# Battery_Management.net
KiCad netlist of a schematic drawn in Altium Designer
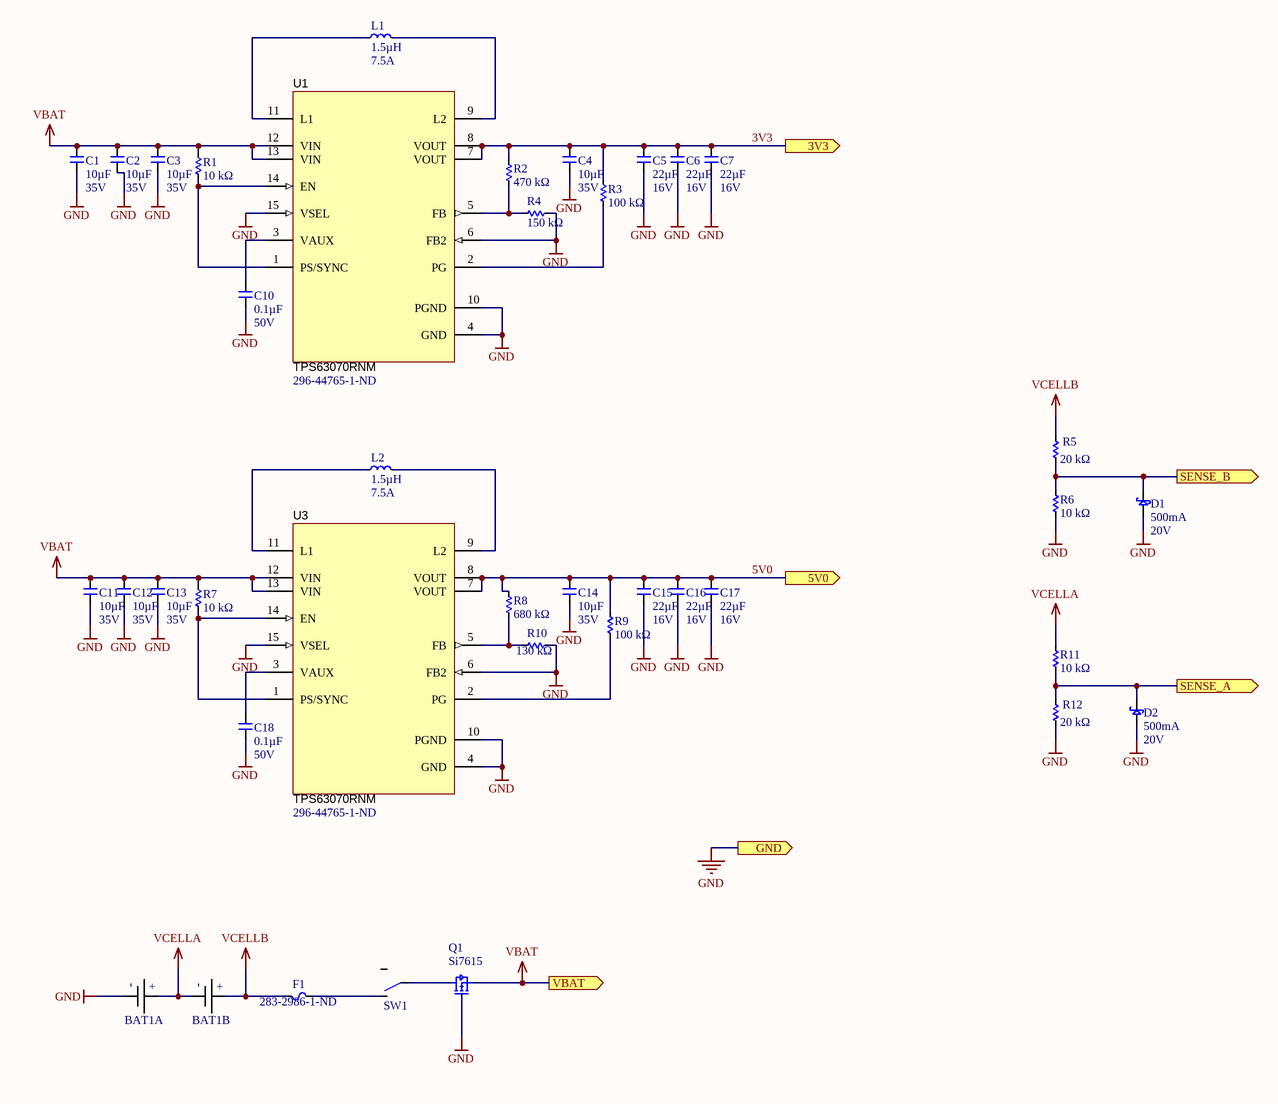
[diagram p0: Battery_Management.SchDoc]

(export (version "E")
  (design (tool "Eeschema 10.0.6"))
  (components
    (comp (ref "BAT1")
      (value "BATT_Clip_Li-Ion_2x")
      (footprint "BATT_18650_KEYSTONE_1048")
      (description "Dual Lithium Ion Cell Holder")
      (fields
        (field (name "MANUFACTURER") "Keystone Electronics")
        (field (name "MANUFACTURER PART NUMBER") "1048P")
      )
      (libsource (lib "connector") (part "BATT_Clip_Li-Ion_2x"))
    )
    (comp (ref "C1")
      (value "__template_cap")
      (footprint "C0603")
      (fields
        (field (name "CAPACITANCE (SHORTHAND)") "10µF")
        (field (name "RATED VOLTAGE") "35V")
        (field (name "MANUFACTURER") "Murata Electronics North America")
      )
      (libsource (lib "passives") (part "__template_cap"))
    )
    (comp (ref "C2")
      (value "__template_cap")
      (footprint "C0603")
      (fields
        (field (name "CAPACITANCE (SHORTHAND)") "10µF")
        (field (name "RATED VOLTAGE") "35V")
        (field (name "MANUFACTURER") "Murata Electronics North America")
      )
      (libsource (lib "passives") (part "__template_cap"))
    )
    (comp (ref "C3")
      (value "__template_cap")
      (footprint "C0603")
      (fields
        (field (name "CAPACITANCE (SHORTHAND)") "10µF")
        (field (name "RATED VOLTAGE") "35V")
        (field (name "MANUFACTURER") "Murata Electronics North America")
      )
      (libsource (lib "passives") (part "__template_cap"))
    )
    (comp (ref "C4")
      (value "__template_cap")
      (footprint "C0603")
      (fields
        (field (name "CAPACITANCE (SHORTHAND)") "10µF")
        (field (name "RATED VOLTAGE") "35V")
        (field (name "MANUFACTURER") "Murata Electronics North America")
      )
      (libsource (lib "passives") (part "__template_cap"))
    )
    (comp (ref "C5")
      (value "__template_cap")
      (footprint "C0603")
      (fields
        (field (name "CAPACITANCE (SHORTHAND)") "22µF")
        (field (name "RATED VOLTAGE") "16V")
        (field (name "MANUFACTURER") "Samsung Electro-Mechanics")
      )
      (libsource (lib "passives") (part "__template_cap"))
    )
    (comp (ref "C6")
      (value "__template_cap")
      (footprint "C0603")
      (fields
        (field (name "CAPACITANCE (SHORTHAND)") "22µF")
        (field (name "RATED VOLTAGE") "16V")
        (field (name "MANUFACTURER") "Samsung Electro-Mechanics")
      )
      (libsource (lib "passives") (part "__template_cap"))
    )
    (comp (ref "C7")
      (value "__template_cap")
      (footprint "C0603")
      (fields
        (field (name "CAPACITANCE (SHORTHAND)") "22µF")
        (field (name "RATED VOLTAGE") "16V")
        (field (name "MANUFACTURER") "Samsung Electro-Mechanics")
      )
      (libsource (lib "passives") (part "__template_cap"))
    )
    (comp (ref "C10")
      (value "__template_cap")
      (footprint "C0603")
      (fields
        (field (name "CAPACITANCE (SHORTHAND)") "0.1µF")
        (field (name "RATED VOLTAGE") "50V")
        (field (name "MANUFACTURER") "Murata Electronics North America")
      )
      (libsource (lib "passives") (part "__template_cap"))
    )
    (comp (ref "C11")
      (value "__template_cap")
      (footprint "C0603")
      (fields
        (field (name "CAPACITANCE (SHORTHAND)") "10µF")
        (field (name "RATED VOLTAGE") "35V")
        (field (name "MANUFACTURER") "Murata Electronics North America")
      )
      (libsource (lib "passives") (part "__template_cap"))
    )
    (comp (ref "C12")
      (value "__template_cap")
      (footprint "C0603")
      (fields
        (field (name "CAPACITANCE (SHORTHAND)") "10µF")
        (field (name "RATED VOLTAGE") "35V")
        (field (name "MANUFACTURER") "Murata Electronics North America")
      )
      (libsource (lib "passives") (part "__template_cap"))
    )
    (comp (ref "C13")
      (value "__template_cap")
      (footprint "C0603")
      (fields
        (field (name "CAPACITANCE (SHORTHAND)") "10µF")
        (field (name "RATED VOLTAGE") "35V")
        (field (name "MANUFACTURER") "Murata Electronics North America")
      )
      (libsource (lib "passives") (part "__template_cap"))
    )
    (comp (ref "C14")
      (value "__template_cap")
      (footprint "C0603")
      (fields
        (field (name "CAPACITANCE (SHORTHAND)") "10µF")
        (field (name "RATED VOLTAGE") "35V")
        (field (name "MANUFACTURER") "Murata Electronics North America")
      )
      (libsource (lib "passives") (part "__template_cap"))
    )
    (comp (ref "C15")
      (value "__template_cap")
      (footprint "C0603")
      (fields
        (field (name "CAPACITANCE (SHORTHAND)") "22µF")
        (field (name "RATED VOLTAGE") "16V")
        (field (name "MANUFACTURER") "Samsung Electro-Mechanics")
      )
      (libsource (lib "passives") (part "__template_cap"))
    )
    (comp (ref "C16")
      (value "__template_cap")
      (footprint "C0603")
      (fields
        (field (name "CAPACITANCE (SHORTHAND)") "22µF")
        (field (name "RATED VOLTAGE") "16V")
        (field (name "MANUFACTURER") "Samsung Electro-Mechanics")
      )
      (libsource (lib "passives") (part "__template_cap"))
    )
    (comp (ref "C17")
      (value "__template_cap")
      (footprint "C0603")
      (fields
        (field (name "CAPACITANCE (SHORTHAND)") "22µF")
        (field (name "RATED VOLTAGE") "16V")
        (field (name "MANUFACTURER") "Samsung Electro-Mechanics")
      )
      (libsource (lib "passives") (part "__template_cap"))
    )
    (comp (ref "C18")
      (value "__template_cap")
      (footprint "C0603")
      (fields
        (field (name "CAPACITANCE (SHORTHAND)") "0.1µF")
        (field (name "RATED VOLTAGE") "50V")
        (field (name "MANUFACTURER") "Murata Electronics North America")
      )
      (libsource (lib "passives") (part "__template_cap"))
    )
    (comp (ref "D1")
      (value "SCHOTTKY_MBR0520L")
      (footprint "SOD123")
      (description "DIODE SCHOTTKY 0.5A 20V SOD-123")
      (fields
        (field (name "MANUFACTURER") "Fairchild Semiconductor")
        (field (name "MANUFACTURER PART NUMBER") "MBR0520L")
        (field (name "CURRENT - AVERAGE RECTIFIED (IO)") "500mA")
        (field (name "VOLTAGE - DC REVERSE (VR) (MAX)") "20V")
      )
      (libsource (lib "SSI") (part "SCHOTTKY_MBR0520L"))
    )
    (comp (ref "D2")
      (value "SCHOTTKY_MBR0520L")
      (footprint "SOD123")
      (description "DIODE SCHOTTKY 0.5A 20V SOD-123")
      (fields
        (field (name "MANUFACTURER") "Fairchild Semiconductor")
        (field (name "MANUFACTURER PART NUMBER") "MBR0520L")
        (field (name "CURRENT - AVERAGE RECTIFIED (IO)") "500mA")
        (field (name "VOLTAGE - DC REVERSE (VR) (MAX)") "20V")
      )
      (libsource (lib "SSI") (part "SCHOTTKY_MBR0520L"))
    )
    (comp (ref "F1")
      (value "__template_fuse")
      (footprint "R1206")
      (fields
        (field (name "SUPPLIER PART NUMBER 1") "283-2986-1-ND")
        (field (name "MANUFACTURER") "Eaton")
        (field (name "MANUFACTURER PART NUMBER") "CC12H5A-TR")
      )
      (libsource (lib "SSI") (part "__template_fuse"))
    )
    (comp (ref "L1")
      (value "IND_IHLP2020CZER1R5M11")
      (footprint "SMD5230")
      (description "INDUCTOR POWER 1.5UH 7.5A SMD")
      (fields
        (field (name "MANUFACTURER") "Vishay Dale")
        (field (name "MANUFACTURER PART NUMBER") "IHLP2020CZER1R5M11")
        (field (name "INDUCTANCE") "1.5µH")
        (field (name "CURRENT RATING") "7.5A")
      )
      (libsource (lib "SSI") (part "IND_IHLP2020CZER1R5M11"))
    )
    (comp (ref "L2")
      (value "IND_IHLP2020CZER1R5M11")
      (footprint "SMD5230")
      (description "INDUCTOR POWER 1.5UH 7.5A SMD")
      (fields
        (field (name "MANUFACTURER") "Vishay Dale")
        (field (name "MANUFACTURER PART NUMBER") "IHLP2020CZER1R5M11")
        (field (name "INDUCTANCE") "1.5µH")
        (field (name "CURRENT RATING") "7.5A")
      )
      (libsource (lib "SSI") (part "IND_IHLP2020CZER1R5M11"))
    )
    (comp (ref "Q1")
      (value "Si7615")
      (footprint "POWERPAK_1212-8_SINGLE")
      (description "MOSFET P-CH 20V 35A PPK")
      (fields
        (field (name "MANUFACTURER") "Vishay Siliconix")
        (field (name "MANUFACTURER PART NUMBER") "SI7615ADN-T1-GE3")
      )
      (libsource (lib "SSI") (part "PFET_SI7615ADN-T1"))
    )
    (comp (ref "R1")
      (value "__template_resistor")
      (footprint "R0603")
      (fields
        (field (name "RESISTANCE") "10 kΩ")
        (field (name "MANUFACTURER PART NUMBER") "RC0603FR-0710KL")
        (field (name "MANUFACTURER") "Yageo")
        (field (name "TOLERANCE") "±1%")
      )
      (libsource (lib "passives") (part "__template_resistor"))
    )
    (comp (ref "R2")
      (value "RC0603FR-07470KL")
      (footprint "R0603")
      (fields
        (field (name "MANUFACTURER") "Yageo")
        (field (name "TOLERANCE") "±1%")
        (field (name "RESISTANCE") "470 kΩ")
      )
      (libsource (lib "passives") (part "__template_resistor"))
    )
    (comp (ref "R3")
      (value "RC0603FR-07100KL")
      (footprint "R0603")
      (fields
        (field (name "MANUFACTURER") "Yageo")
        (field (name "TOLERANCE") "±1%")
        (field (name "RESISTANCE") "100 kΩ")
      )
      (libsource (lib "passives") (part "__template_resistor"))
    )
    (comp (ref "R4")
      (value "RC0603FR-07150KL")
      (footprint "R0603")
      (fields
        (field (name "MANUFACTURER") "Yageo")
        (field (name "TOLERANCE") "±1%")
        (field (name "RESISTANCE") "150 kΩ")
      )
      (libsource (lib "passives") (part "__template_resistor"))
    )
    (comp (ref "R5")
      (value "__template_resistor")
      (footprint "R0603")
      (fields
        (field (name "RESISTANCE") "20 kΩ")
        (field (name "MANUFACTURER PART NUMBER") "RC0603FR-0720KL")
        (field (name "MANUFACTURER") "Yageo")
        (field (name "TOLERANCE") "±1%")
      )
      (libsource (lib "passives") (part "__template_resistor"))
    )
    (comp (ref "R6")
      (value "__template_resistor")
      (footprint "R0603")
      (fields
        (field (name "RESISTANCE") "10 kΩ")
        (field (name "MANUFACTURER PART NUMBER") "RC0603FR-0710KL")
        (field (name "MANUFACTURER") "Yageo")
        (field (name "TOLERANCE") "±1%")
      )
      (libsource (lib "passives") (part "__template_resistor"))
    )
    (comp (ref "R7")
      (value "__template_resistor")
      (footprint "R0603")
      (fields
        (field (name "RESISTANCE") "10 kΩ")
        (field (name "MANUFACTURER PART NUMBER") "RC0603FR-0710KL")
        (field (name "MANUFACTURER") "Yageo")
        (field (name "TOLERANCE") "±1%")
      )
      (libsource (lib "passives") (part "__template_resistor"))
    )
    (comp (ref "R8")
      (value "RC0603FR-07680KL")
      (footprint "R0603")
      (fields
        (field (name "MANUFACTURER") "Yageo")
        (field (name "TOLERANCE") "±1%")
        (field (name "RESISTANCE") "680 kΩ")
      )
      (libsource (lib "passives") (part "__template_resistor"))
    )
    (comp (ref "R9")
      (value "RC0603FR-07100KL")
      (footprint "R0603")
      (fields
        (field (name "MANUFACTURER") "Yageo")
        (field (name "TOLERANCE") "±1%")
        (field (name "RESISTANCE") "100 kΩ")
      )
      (libsource (lib "passives") (part "__template_resistor"))
    )
    (comp (ref "R10")
      (value "RC0603FR-07130KL")
      (footprint "R0603")
      (fields
        (field (name "MANUFACTURER") "Yageo")
        (field (name "TOLERANCE") "±1%")
        (field (name "RESISTANCE") "130 kΩ")
      )
      (libsource (lib "passives") (part "__template_resistor"))
    )
    (comp (ref "R11")
      (value "__template_resistor")
      (footprint "R0603")
      (fields
        (field (name "RESISTANCE") "10 kΩ")
        (field (name "MANUFACTURER PART NUMBER") "RC0603FR-0710KL")
        (field (name "MANUFACTURER") "Yageo")
        (field (name "TOLERANCE") "±1%")
      )
      (libsource (lib "passives") (part "__template_resistor"))
    )
    (comp (ref "R12")
      (value "__template_resistor")
      (footprint "R0603")
      (fields
        (field (name "RESISTANCE") "20 kΩ")
        (field (name "MANUFACTURER PART NUMBER") "RC0603FR-0720KL")
        (field (name "MANUFACTURER") "Yageo")
        (field (name "TOLERANCE") "±1%")
      )
      (libsource (lib "passives") (part "__template_resistor"))
    )
    (comp (ref "SW1")
      (value "~")
      (footprint "SWITCH_500SSP1S1M6QEA")
      (description "SWITCH SLIDE SPDT R/A 5A")
      (fields
        (field (name "MANUFACTURER") "E-Switch")
        (field (name "MANUFACTURER PART NUMBER") "500SSP1S1M6QEA")
      )
      (libsource (lib "SSI") (part "SWITCH_500SSP1S1M6QEA"))
    )
    (comp (ref "U1")
      (value "TPS63070RNM")
      (footprint "TPS63070")
      (description "BUCKBOOST TPS63070RNM, RNM0015A")
      (fields
        (field (name "MANUFACTURER") "Texas Instruments")
        (field (name "SUPPLIER PART NUMBER 1") "296-44765-1-ND")
        (field (name "SYMBOLCREATOR") "Altium")
        (field (name "PUBLISHER") "Texas Instruments")
      )
      (libsource (lib "SSI") (part "TPS63070RNM"))
    )
    (comp (ref "U3")
      (value "TPS63070RNM")
      (footprint "TPS63070")
      (description "BUCKBOOST TPS63070RNM, RNM0015A")
      (fields
        (field (name "MANUFACTURER") "Texas Instruments")
        (field (name "SUPPLIER PART NUMBER 1") "296-44765-1-ND")
        (field (name "SYMBOLCREATOR") "Altium")
        (field (name "PUBLISHER") "Texas Instruments")
      )
      (libsource (lib "SSI") (part "TPS63070RNM"))
    )
  )
  (nets
    (net (code "1") (name "/3V3") (class "Default")
      (node (ref "C4") (pin "1") (pintype "passive"))
      (node (ref "C5") (pin "1") (pintype "passive"))
      (node (ref "C6") (pin "1") (pintype "passive"))
      (node (ref "C7") (pin "1") (pintype "passive"))
      (node (ref "R2") (pin "2") (pintype "passive"))
      (node (ref "R3") (pin "2") (pintype "passive"))
      (node (ref "U1") (pin "7") (pinfunction "VOUT_7") (pintype "power_in"))
      (node (ref "U1") (pin "8") (pinfunction "VOUT_8") (pintype "power_in"))
    )
    (net (code "2") (name "/5V0") (class "Default")
      (node (ref "C14") (pin "1") (pintype "passive"))
      (node (ref "C15") (pin "1") (pintype "passive"))
      (node (ref "C16") (pin "1") (pintype "passive"))
      (node (ref "C17") (pin "1") (pintype "passive"))
      (node (ref "R8") (pin "2") (pintype "passive"))
      (node (ref "R9") (pin "2") (pintype "passive"))
      (node (ref "U3") (pin "7") (pinfunction "VOUT_7") (pintype "power_in"))
      (node (ref "U3") (pin "8") (pinfunction "VOUT_8") (pintype "power_in"))
    )
    (net (code "3") (name "/SENSE_A") (class "Default")
      (node (ref "D2") (pin "2") (pintype "passive"))
      (node (ref "R11") (pin "1") (pintype "passive"))
      (node (ref "R12") (pin "2") (pintype "passive"))
    )
    (net (code "4") (name "/SENSE_B") (class "Default")
      (node (ref "D1") (pin "2") (pintype "passive"))
      (node (ref "R5") (pin "1") (pintype "passive"))
      (node (ref "R6") (pin "2") (pintype "passive"))
    )
    (net (code "5") (name "GND") (class "Default")
      (node (ref "BAT1") (pin "CELL1-") (pinfunction "CELL1-_CELL1-") (pintype "passive"))
      (node (ref "C1") (pin "2") (pintype "passive"))
      (node (ref "C10") (pin "2") (pintype "passive"))
      (node (ref "C11") (pin "2") (pintype "passive"))
      (node (ref "C12") (pin "2") (pintype "passive"))
      (node (ref "C13") (pin "2") (pintype "passive"))
      (node (ref "C14") (pin "2") (pintype "passive"))
      (node (ref "C15") (pin "2") (pintype "passive"))
      (node (ref "C16") (pin "2") (pintype "passive"))
      (node (ref "C17") (pin "2") (pintype "passive"))
      (node (ref "C18") (pin "2") (pintype "passive"))
      (node (ref "C2") (pin "2") (pintype "passive"))
      (node (ref "C3") (pin "2") (pintype "passive"))
      (node (ref "C4") (pin "2") (pintype "passive"))
      (node (ref "C5") (pin "2") (pintype "passive"))
      (node (ref "C6") (pin "2") (pintype "passive"))
      (node (ref "C7") (pin "2") (pintype "passive"))
      (node (ref "D1") (pin "1") (pintype "passive"))
      (node (ref "D2") (pin "1") (pintype "passive"))
      (node (ref "Q1") (pin "1") (pintype "passive"))
      (node (ref "R10") (pin "2") (pintype "passive"))
      (node (ref "R12") (pin "1") (pintype "passive"))
      (node (ref "R4") (pin "2") (pintype "passive"))
      (node (ref "R6") (pin "1") (pintype "passive"))
      (node (ref "U1") (pin "10") (pinfunction "PGND_10") (pintype "power_in"))
      (node (ref "U1") (pin "15") (pinfunction "VSEL_15") (pintype "input"))
      (node (ref "U1") (pin "4") (pinfunction "GND_4") (pintype "power_in"))
      (node (ref "U1") (pin "6") (pinfunction "FB2_6") (pintype "input"))
      (node (ref "U3") (pin "10") (pinfunction "PGND_10") (pintype "power_in"))
      (node (ref "U3") (pin "15") (pinfunction "VSEL_15") (pintype "input"))
      (node (ref "U3") (pin "4") (pinfunction "GND_4") (pintype "power_in"))
      (node (ref "U3") (pin "6") (pinfunction "FB2_6") (pintype "input"))
    )
    (net (code "6") (name "Net-(F1-Pad2)") (class "Default")
      (node (ref "F1") (pin "2") (pintype "passive"))
      (node (ref "SW1") (pin "3") (pintype "passive"))
    )
    (net (code "7") (name "Net-(Q1-Pad3)") (class "Default")
      (node (ref "Q1") (pin "3") (pintype "passive"))
      (node (ref "SW1") (pin "2") (pintype "passive"))
    )
    (net (code "8") (name "Net-(U1-EN)") (class "Default")
      (node (ref "R1") (pin "1") (pintype "passive"))
      (node (ref "U1") (pin "1") (pinfunction "PS/SYNC_1") (pintype "passive"))
      (node (ref "U1") (pin "14") (pinfunction "EN_14") (pintype "input"))
    )
    (net (code "9") (name "Net-(U1-FB)") (class "Default")
      (node (ref "R2") (pin "1") (pintype "passive"))
      (node (ref "R4") (pin "1") (pintype "passive"))
      (node (ref "U1") (pin "5") (pinfunction "FB_5") (pintype "output"))
    )
    (net (code "10") (name "Net-(U1-L1)") (class "Default")
      (node (ref "L1") (pin "1") (pintype "passive"))
      (node (ref "U1") (pin "11") (pinfunction "L1_11") (pintype "passive"))
    )
    (net (code "11") (name "Net-(U1-L2)") (class "Default")
      (node (ref "L1") (pin "2") (pintype "passive"))
      (node (ref "U1") (pin "9") (pinfunction "L2_9") (pintype "passive"))
    )
    (net (code "12") (name "Net-(U1-PG)") (class "Default")
      (node (ref "R3") (pin "1") (pintype "passive"))
      (node (ref "U1") (pin "2") (pinfunction "PG_2") (pintype "open_collector"))
    )
    (net (code "13") (name "Net-(U1-VAUX)") (class "Default")
      (node (ref "C10") (pin "1") (pintype "passive"))
      (node (ref "U1") (pin "3") (pinfunction "VAUX_3") (pintype "passive"))
    )
    (net (code "14") (name "Net-(U3-EN)") (class "Default")
      (node (ref "R7") (pin "1") (pintype "passive"))
      (node (ref "U3") (pin "1") (pinfunction "PS/SYNC_1") (pintype "passive"))
      (node (ref "U3") (pin "14") (pinfunction "EN_14") (pintype "input"))
    )
    (net (code "15") (name "Net-(U3-FB)") (class "Default")
      (node (ref "R10") (pin "1") (pintype "passive"))
      (node (ref "R8") (pin "1") (pintype "passive"))
      (node (ref "U3") (pin "5") (pinfunction "FB_5") (pintype "output"))
    )
    (net (code "16") (name "Net-(U3-L1)") (class "Default")
      (node (ref "L2") (pin "1") (pintype "passive"))
      (node (ref "U3") (pin "11") (pinfunction "L1_11") (pintype "passive"))
    )
    (net (code "17") (name "Net-(U3-L2)") (class "Default")
      (node (ref "L2") (pin "2") (pintype "passive"))
      (node (ref "U3") (pin "9") (pinfunction "L2_9") (pintype "passive"))
    )
    (net (code "18") (name "Net-(U3-PG)") (class "Default")
      (node (ref "R9") (pin "1") (pintype "passive"))
      (node (ref "U3") (pin "2") (pinfunction "PG_2") (pintype "open_collector"))
    )
    (net (code "19") (name "Net-(U3-VAUX)") (class "Default")
      (node (ref "C18") (pin "1") (pintype "passive"))
      (node (ref "U3") (pin "3") (pinfunction "VAUX_3") (pintype "passive"))
    )
    (net (code "20") (name "VBAT") (class "Default")
      (node (ref "C1") (pin "1") (pintype "passive"))
      (node (ref "C11") (pin "1") (pintype "passive"))
      (node (ref "C12") (pin "1") (pintype "passive"))
      (node (ref "C13") (pin "1") (pintype "passive"))
      (node (ref "C2") (pin "1") (pintype "passive"))
      (node (ref "C3") (pin "1") (pintype "passive"))
      (node (ref "Q1") (pin "2") (pintype "passive"))
      (node (ref "R1") (pin "2") (pintype "passive"))
      (node (ref "R7") (pin "2") (pintype "passive"))
      (node (ref "U1") (pin "12") (pinfunction "VIN_12") (pintype "power_in"))
      (node (ref "U1") (pin "13") (pinfunction "VIN_13") (pintype "power_in"))
      (node (ref "U3") (pin "12") (pinfunction "VIN_12") (pintype "power_in"))
      (node (ref "U3") (pin "13") (pinfunction "VIN_13") (pintype "power_in"))
    )
    (net (code "21") (name "VCELLA") (class "Default")
      (node (ref "BAT1") (pin "CELL1+") (pinfunction "CELL1+_CELL1+") (pintype "passive"))
      (node (ref "BAT1") (pin "CELL2-") (pinfunction "CELL2-_CELL2-") (pintype "passive"))
      (node (ref "R11") (pin "2") (pintype "passive"))
    )
    (net (code "22") (name "VCELLB") (class "Default")
      (node (ref "BAT1") (pin "CELL2+") (pinfunction "CELL2+_CELL2+") (pintype "passive"))
      (node (ref "F1") (pin "1") (pintype "passive"))
      (node (ref "R5") (pin "2") (pintype "passive"))
    )
    (net (code "23") (name "unconnected-(SW1-Pad1)") (class "Default")
      (node (ref "SW1") (pin "1") (pintype "passive"))
    )
  )
)
